# PCE128_rev_C2.net
KiCad netlist of a schematic drawn in EAGLE
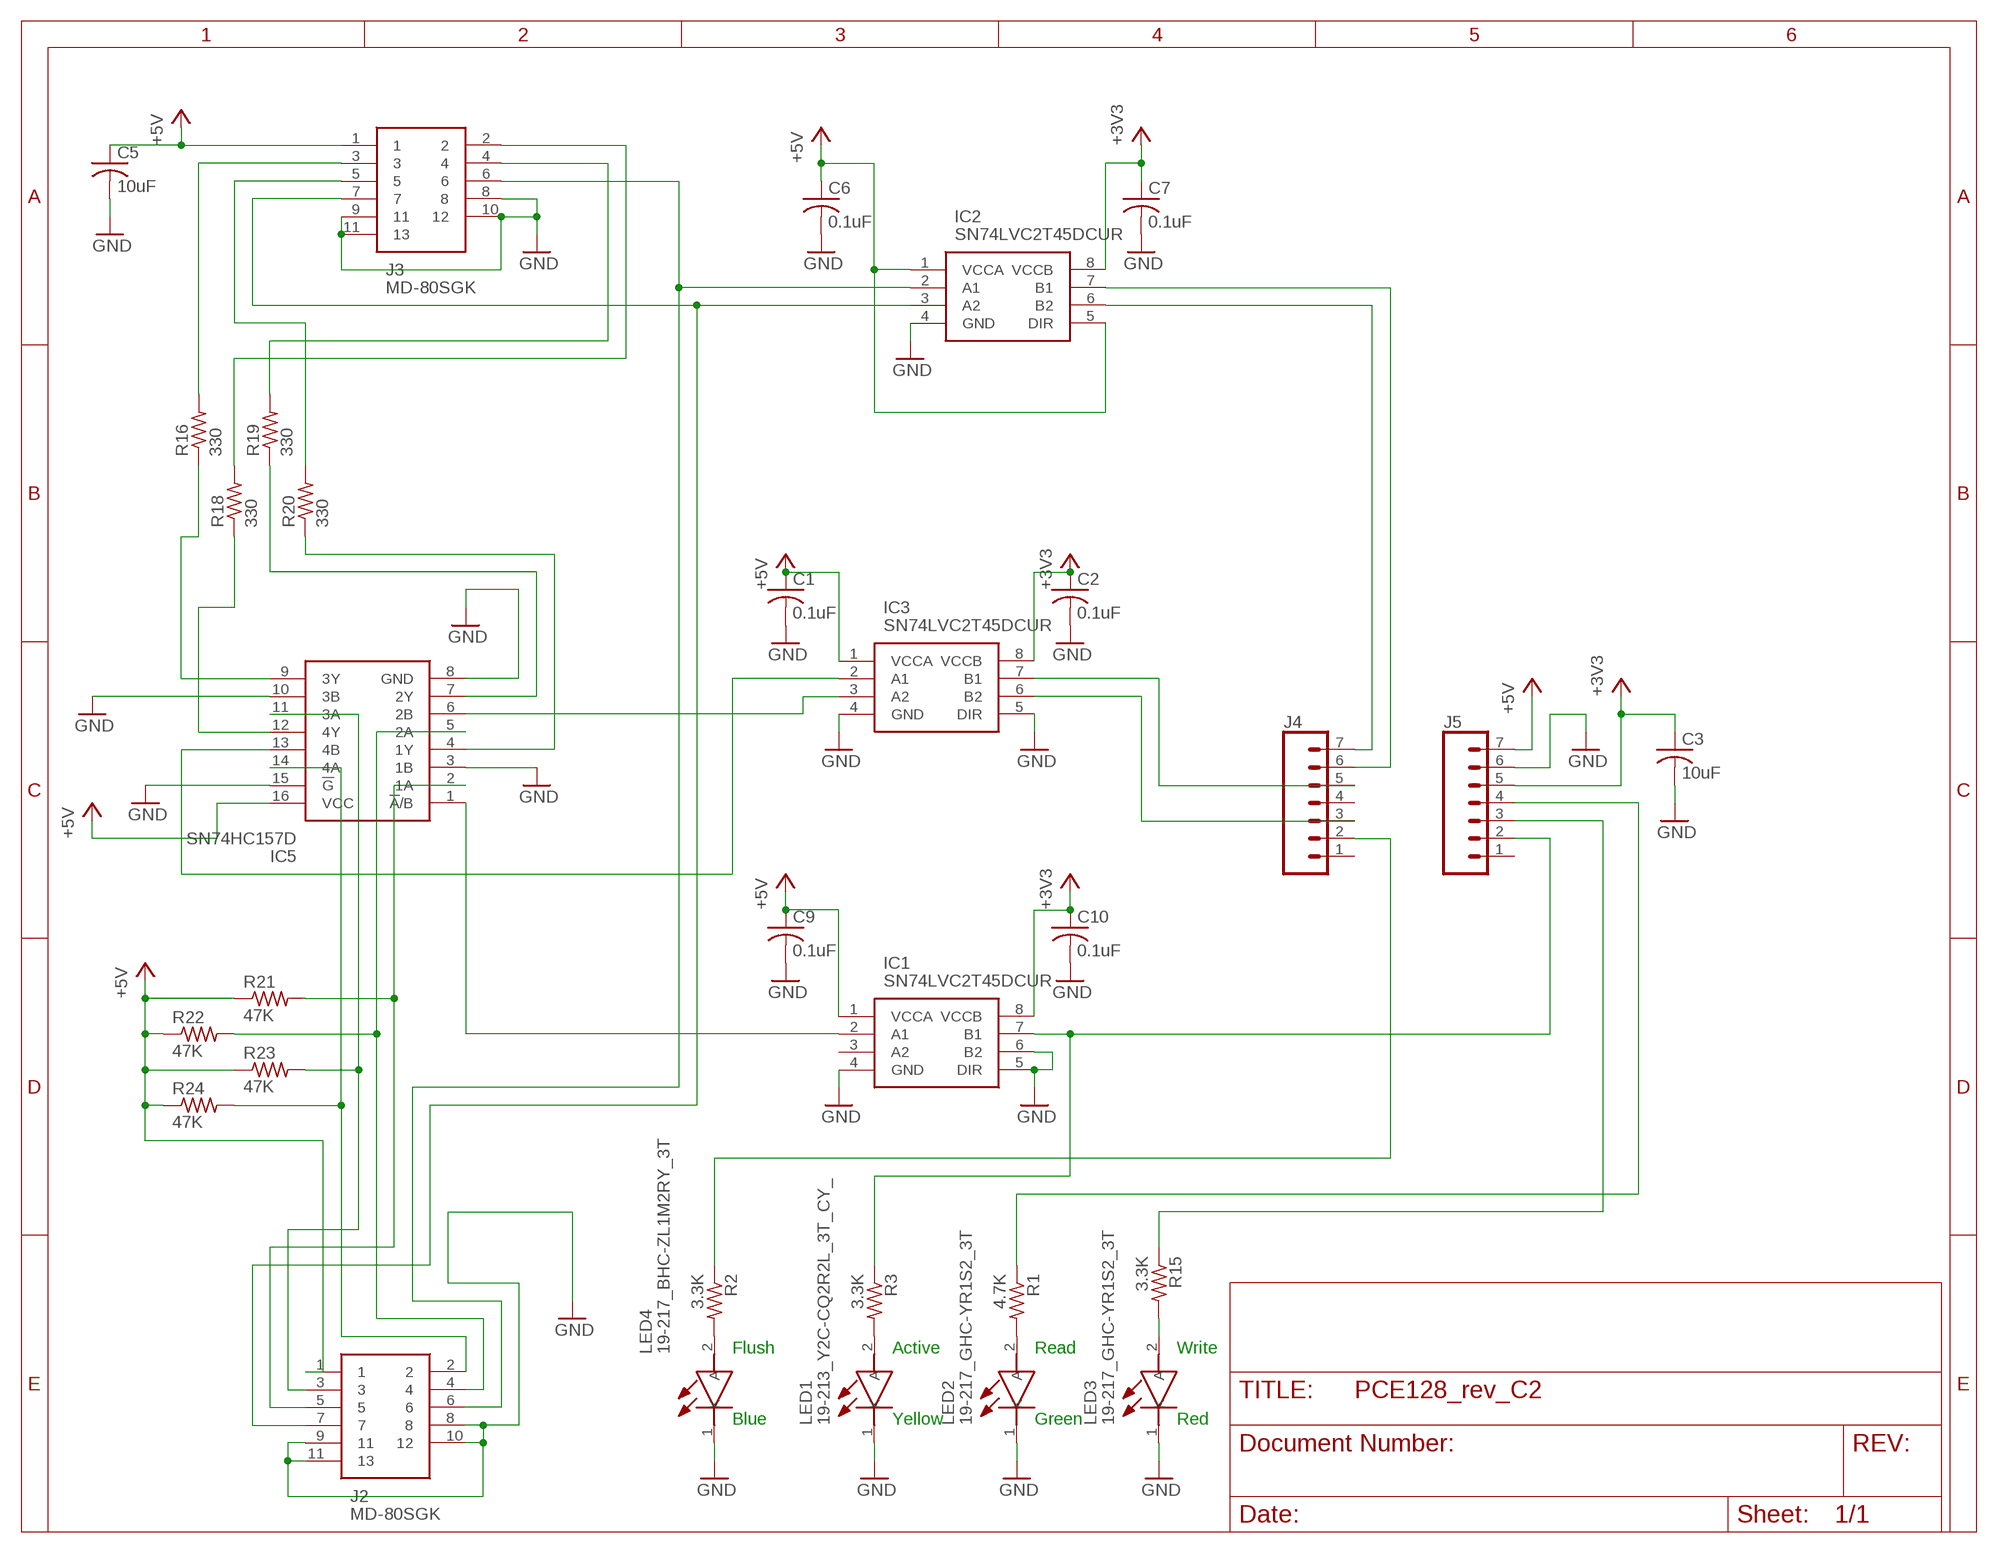
[diagram p0: schematic, sheet 1]

(export (version "E")
  (design (tool "Eeschema 10.0.6"))
  (components
    (comp (ref "C1")
      (value "0.1uF")
      (footprint "eagle-import:C0402")
      (libsource (lib "eagle-import") (part "C-USC0402"))
    )
    (comp (ref "C2")
      (value "0.1uF")
      (footprint "eagle-import:C0402")
      (libsource (lib "eagle-import") (part "C-USC0402"))
    )
    (comp (ref "C3")
      (value "10uF")
      (footprint "eagle-import:C0805")
      (libsource (lib "eagle-import") (part "C-USC0805"))
    )
    (comp (ref "C5")
      (value "10uF")
      (footprint "eagle-import:C0805")
      (libsource (lib "eagle-import") (part "C-USC0805"))
    )
    (comp (ref "C6")
      (value "0.1uF")
      (footprint "eagle-import:C0402")
      (libsource (lib "eagle-import") (part "C-USC0402"))
    )
    (comp (ref "C7")
      (value "0.1uF")
      (footprint "eagle-import:C0402")
      (libsource (lib "eagle-import") (part "C-USC0402"))
    )
    (comp (ref "C9")
      (value "0.1uF")
      (footprint "eagle-import:C0402")
      (libsource (lib "eagle-import") (part "C-USC0402"))
    )
    (comp (ref "C10")
      (value "0.1uF")
      (footprint "eagle-import:C0402")
      (libsource (lib "eagle-import") (part "C-USC0402"))
    )
    (comp (ref "IC1")
      (value "SN74LVC2T45DCUR")
      (footprint "eagle-import:SOP50P310X90-8N")
      (fields (field (name "MOUSER_PART_NUMBER") "595-SN74LVC2T45DCUR"))
      (libsource (lib "eagle-import") (part "SN74LVC2T45DCUR"))
    )
    (comp (ref "IC2")
      (value "SN74LVC2T45DCUR")
      (footprint "eagle-import:SOP50P310X90-8N")
      (fields (field (name "MOUSER_PART_NUMBER") "595-SN74LVC2T45DCUR"))
      (libsource (lib "eagle-import") (part "SN74LVC2T45DCUR"))
    )
    (comp (ref "IC3")
      (value "SN74LVC2T45DCUR")
      (footprint "eagle-import:SOP50P310X90-8N")
      (fields (field (name "MOUSER_PART_NUMBER") "595-SN74LVC2T45DCUR"))
      (libsource (lib "eagle-import") (part "SN74LVC2T45DCUR"))
    )
    (comp (ref "IC5")
      (value "SN74HC157D")
      (footprint "eagle-import:SOIC127P600X175-16N")
      (fields (field (name "MOUSER_PART_NUMBER") "595-SN74HC157D"))
      (libsource (lib "eagle-import") (part "SN74HC157D"))
    )
    (comp (ref "J2")
      (value "MD-80SGK")
      (footprint "eagle-import:MD80SGK")
      (fields (field (name "MOUSER_PART_NUMBER") "490-MD-80SGK"))
      (libsource (lib "eagle-import") (part "MD-80SGK"))
    )
    (comp (ref "J3")
      (value "MD-80SGK")
      (footprint "eagle-import:MD80SGK")
      (fields (field (name "MOUSER_PART_NUMBER") "490-MD-80SGK"))
      (libsource (lib "eagle-import") (part "MD-80SGK"))
    )
    (comp (ref "J4")
      (value "CONN_07NO_SILK")
      (footprint "eagle-import:1X07_NO_SILK")
      (libsource (lib "eagle-import") (part "CONN_07NO_SILK"))
    )
    (comp (ref "J5")
      (value "CONN_07NO_SILK")
      (footprint "eagle-import:1X07_NO_SILK")
      (libsource (lib "eagle-import") (part "CONN_07NO_SILK"))
    )
    (comp (ref "LED1")
      (value "19-213_Y2C-CQ2R2L_3T_CY_")
      (footprint "eagle-import:LEDC1608X50N")
      (fields (field (name "ARROW_PART_NUMBER") "19-213/Y2C-CQ2R2L/3T(CY)"))
      (libsource (lib "eagle-import") (part "19-213_Y2C-CQ2R2L_3T_CY_"))
    )
    (comp (ref "LED2")
      (value "19-217_GHC-YR1S2_3T")
      (footprint "eagle-import:LEDC1608X50N")
      (fields
        (field (name "ARROW_PART_NUMBER") "19-217/GHC-YR1S2/3T")
        (field (name "MOUSER_PART_NUMBER") "638-19217GHCYR1S23T")
      )
      (libsource (lib "eagle-import") (part "19-217_GHC-YR1S2_3T"))
    )
    (comp (ref "LED3")
      (value "19-217_GHC-YR1S2_3T")
      (footprint "eagle-import:LEDC1608X50N")
      (fields
        (field (name "ARROW_PART_NUMBER") "19-217/GHC-YR1S2/3T")
        (field (name "MOUSER_PART_NUMBER") "638-19217GHCYR1S23T")
        (field (name "MANUFACTURER_NAME") "Hubei Kento")
        (field (name "MANUFACTURER_PART_NUMBER") "KT-0603R")
      )
      (libsource (lib "eagle-import") (part "19-217_GHC-YR1S2_3T"))
    )
    (comp (ref "LED4")
      (value "19-217_BHC-ZL1M2RY_3T")
      (footprint "eagle-import:LEDC1608X50N")
      (libsource (lib "eagle-import") (part "19-217_BHC-ZL1M2RY_3T"))
    )
    (comp (ref "R1")
      (value "4.7K")
      (footprint "eagle-import:R0402")
      (libsource (lib "eagle-import") (part "R-US_R0402"))
    )
    (comp (ref "R2")
      (value "3.3K")
      (footprint "eagle-import:R0402")
      (libsource (lib "eagle-import") (part "R-US_R0402"))
    )
    (comp (ref "R3")
      (value "3.3K")
      (footprint "eagle-import:R0402")
      (libsource (lib "eagle-import") (part "R-US_R0402"))
    )
    (comp (ref "R15")
      (value "3.3K")
      (footprint "eagle-import:R0402")
      (libsource (lib "eagle-import") (part "R-US_R0402"))
    )
    (comp (ref "R16")
      (value "330")
      (footprint "eagle-import:R0402")
      (libsource (lib "eagle-import") (part "R-US_R0402"))
    )
    (comp (ref "R18")
      (value "330")
      (footprint "eagle-import:R0402")
      (libsource (lib "eagle-import") (part "R-US_R0402"))
    )
    (comp (ref "R19")
      (value "330")
      (footprint "eagle-import:R0402")
      (libsource (lib "eagle-import") (part "R-US_R0402"))
    )
    (comp (ref "R20")
      (value "330")
      (footprint "eagle-import:R0402")
      (libsource (lib "eagle-import") (part "R-US_R0402"))
    )
    (comp (ref "R21")
      (value "47K")
      (footprint "eagle-import:R0402")
      (libsource (lib "eagle-import") (part "R-US_R0402"))
    )
    (comp (ref "R22")
      (value "47K")
      (footprint "eagle-import:R0402")
      (libsource (lib "eagle-import") (part "R-US_R0402"))
    )
    (comp (ref "R23")
      (value "47K")
      (footprint "eagle-import:R0402")
      (libsource (lib "eagle-import") (part "R-US_R0402"))
    )
    (comp (ref "R24")
      (value "47K")
      (footprint "eagle-import:R0402")
      (libsource (lib "eagle-import") (part "R-US_R0402"))
    )
  )
  (nets
    (net (code "1") (name "+3V3") (class "Default")
      (node (ref "C10") (pin "1") (pinfunction "1_1") (pintype "passive"))
      (node (ref "C2") (pin "1") (pinfunction "1_1") (pintype "passive"))
      (node (ref "C3") (pin "1") (pinfunction "1_1") (pintype "passive"))
      (node (ref "C7") (pin "1") (pinfunction "1_1") (pintype "passive"))
      (node (ref "IC1") (pin "8") (pinfunction "VCCB_8") (pintype "bidirectional"))
      (node (ref "IC2") (pin "8") (pinfunction "VCCB_8") (pintype "bidirectional"))
      (node (ref "IC3") (pin "8") (pinfunction "VCCB_8") (pintype "bidirectional"))
      (node (ref "J5") (pin "5") (pinfunction "5_5") (pintype "passive"))
    )
    (net (code "2") (name "+5V") (class "Default")
      (node (ref "C1") (pin "1") (pinfunction "1_1") (pintype "passive"))
      (node (ref "C5") (pin "1") (pinfunction "1_1") (pintype "passive"))
      (node (ref "C6") (pin "1") (pinfunction "1_1") (pintype "passive"))
      (node (ref "C9") (pin "1") (pinfunction "1_1") (pintype "passive"))
      (node (ref "IC1") (pin "1") (pinfunction "VCCA_1") (pintype "bidirectional"))
      (node (ref "IC2") (pin "1") (pinfunction "VCCA_1") (pintype "bidirectional"))
      (node (ref "IC2") (pin "5") (pinfunction "DIR_5") (pintype "bidirectional"))
      (node (ref "IC3") (pin "1") (pinfunction "VCCA_1") (pintype "bidirectional"))
      (node (ref "IC5") (pin "16") (pinfunction "VCC_16") (pintype "bidirectional"))
      (node (ref "J2") (pin "1") (pinfunction "1_1") (pintype "bidirectional"))
      (node (ref "J3") (pin "1") (pinfunction "1_1") (pintype "bidirectional"))
      (node (ref "J5") (pin "7") (pinfunction "7_7") (pintype "passive"))
      (node (ref "R21") (pin "1") (pinfunction "1_1") (pintype "passive"))
      (node (ref "R22") (pin "1") (pinfunction "1_1") (pintype "passive"))
      (node (ref "R23") (pin "1") (pinfunction "1_1") (pintype "passive"))
      (node (ref "R24") (pin "1") (pinfunction "1_1") (pintype "passive"))
    )
    (net (code "3") (name "GND") (class "Default")
      (node (ref "C1") (pin "2") (pinfunction "2_2") (pintype "passive"))
      (node (ref "C10") (pin "2") (pinfunction "2_2") (pintype "passive"))
      (node (ref "C2") (pin "2") (pinfunction "2_2") (pintype "passive"))
      (node (ref "C3") (pin "2") (pinfunction "2_2") (pintype "passive"))
      (node (ref "C5") (pin "2") (pinfunction "2_2") (pintype "passive"))
      (node (ref "C6") (pin "2") (pinfunction "2_2") (pintype "passive"))
      (node (ref "C7") (pin "2") (pinfunction "2_2") (pintype "passive"))
      (node (ref "C9") (pin "2") (pinfunction "2_2") (pintype "passive"))
      (node (ref "IC1") (pin "4") (pinfunction "GND_4") (pintype "bidirectional"))
      (node (ref "IC1") (pin "5") (pinfunction "DIR_5") (pintype "bidirectional"))
      (node (ref "IC1") (pin "6") (pinfunction "B2_6") (pintype "bidirectional"))
      (node (ref "IC2") (pin "4") (pinfunction "GND_4") (pintype "bidirectional"))
      (node (ref "IC3") (pin "4") (pinfunction "GND_4") (pintype "bidirectional"))
      (node (ref "IC3") (pin "5") (pinfunction "DIR_5") (pintype "bidirectional"))
      (node (ref "IC5") (pin "10") (pinfunction "3B_10") (pintype "bidirectional"))
      (node (ref "IC5") (pin "15") (pinfunction "~{G}_15") (pintype "bidirectional"))
      (node (ref "IC5") (pin "3") (pinfunction "1B_3") (pintype "bidirectional"))
      (node (ref "IC5") (pin "8") (pinfunction "GND_8") (pintype "bidirectional"))
      (node (ref "J2") (pin "10") (pinfunction "12_10") (pintype "bidirectional"))
      (node (ref "J2") (pin "11") (pinfunction "13_11") (pintype "bidirectional"))
      (node (ref "J2") (pin "8") (pinfunction "8_8") (pintype "bidirectional"))
      (node (ref "J2") (pin "9") (pinfunction "11_9") (pintype "bidirectional"))
      (node (ref "J3") (pin "10") (pinfunction "12_10") (pintype "bidirectional"))
      (node (ref "J3") (pin "11") (pinfunction "13_11") (pintype "bidirectional"))
      (node (ref "J3") (pin "8") (pinfunction "8_8") (pintype "bidirectional"))
      (node (ref "J3") (pin "9") (pinfunction "11_9") (pintype "bidirectional"))
      (node (ref "J5") (pin "6") (pinfunction "6_6") (pintype "passive"))
      (node (ref "LED1") (pin "1") (pinfunction "K_1") (pintype "bidirectional"))
      (node (ref "LED2") (pin "1") (pinfunction "K_1") (pintype "bidirectional"))
      (node (ref "LED3") (pin "1") (pinfunction "K_1") (pintype "bidirectional"))
      (node (ref "LED4") (pin "1") (pinfunction "K_1") (pintype "bidirectional"))
    )
    (net (code "4") (name "Net-(IC1-A1)") (class "Default")
      (node (ref "IC1") (pin "2") (pinfunction "A1_2") (pintype "bidirectional"))
      (node (ref "IC5") (pin "1") (pinfunction "~{A}/B_1") (pintype "bidirectional"))
    )
    (net (code "5") (name "Net-(IC1-B1)") (class "Default")
      (node (ref "IC1") (pin "7") (pinfunction "B1_7") (pintype "bidirectional"))
      (node (ref "J5") (pin "2") (pinfunction "2_2") (pintype "passive"))
      (node (ref "R3") (pin "1") (pinfunction "1_1") (pintype "passive"))
    )
    (net (code "6") (name "Net-(IC2-A1)") (class "Default")
      (node (ref "IC2") (pin "2") (pinfunction "A1_2") (pintype "bidirectional"))
      (node (ref "J2") (pin "6") (pinfunction "6_6") (pintype "bidirectional"))
      (node (ref "J3") (pin "6") (pinfunction "6_6") (pintype "bidirectional"))
    )
    (net (code "7") (name "Net-(IC2-A2)") (class "Default")
      (node (ref "IC2") (pin "3") (pinfunction "A2_3") (pintype "bidirectional"))
      (node (ref "J2") (pin "7") (pinfunction "7_7") (pintype "bidirectional"))
      (node (ref "J3") (pin "7") (pinfunction "7_7") (pintype "bidirectional"))
    )
    (net (code "8") (name "Net-(IC2-B1)") (class "Default")
      (node (ref "IC2") (pin "7") (pinfunction "B1_7") (pintype "bidirectional"))
      (node (ref "J4") (pin "6") (pinfunction "6_6") (pintype "passive"))
    )
    (net (code "9") (name "Net-(IC2-B2)") (class "Default")
      (node (ref "IC2") (pin "6") (pinfunction "B2_6") (pintype "bidirectional"))
      (node (ref "J4") (pin "7") (pinfunction "7_7") (pintype "passive"))
    )
    (net (code "10") (name "Net-(IC3-A1)") (class "Default")
      (node (ref "IC3") (pin "2") (pinfunction "A1_2") (pintype "bidirectional"))
      (node (ref "IC5") (pin "13") (pinfunction "4B_13") (pintype "bidirectional"))
    )
    (net (code "11") (name "Net-(IC3-A2)") (class "Default")
      (node (ref "IC3") (pin "3") (pinfunction "A2_3") (pintype "bidirectional"))
      (node (ref "IC5") (pin "6") (pinfunction "2B_6") (pintype "bidirectional"))
    )
    (net (code "12") (name "Net-(IC3-B1)") (class "Default")
      (node (ref "IC3") (pin "7") (pinfunction "B1_7") (pintype "bidirectional"))
      (node (ref "J4") (pin "5") (pinfunction "5_5") (pintype "passive"))
    )
    (net (code "13") (name "Net-(IC3-B2)") (class "Default")
      (node (ref "IC3") (pin "6") (pinfunction "B2_6") (pintype "bidirectional"))
      (node (ref "J4") (pin "3") (pinfunction "3_3") (pintype "passive"))
    )
    (net (code "14") (name "Net-(IC5-1A)") (class "Default")
      (node (ref "IC5") (pin "2") (pinfunction "1A_2") (pintype "bidirectional"))
      (node (ref "J2") (pin "5") (pinfunction "5_5") (pintype "bidirectional"))
      (node (ref "R21") (pin "2") (pinfunction "2_2") (pintype "passive"))
    )
    (net (code "15") (name "Net-(IC5-1Y)") (class "Default")
      (node (ref "IC5") (pin "4") (pinfunction "1Y_4") (pintype "bidirectional"))
      (node (ref "R20") (pin "1") (pinfunction "1_1") (pintype "passive"))
    )
    (net (code "16") (name "Net-(IC5-2A)") (class "Default")
      (node (ref "IC5") (pin "5") (pinfunction "2A_5") (pintype "bidirectional"))
      (node (ref "J2") (pin "4") (pinfunction "4_4") (pintype "bidirectional"))
      (node (ref "R22") (pin "2") (pinfunction "2_2") (pintype "passive"))
    )
    (net (code "17") (name "Net-(IC5-2Y)") (class "Default")
      (node (ref "IC5") (pin "7") (pinfunction "2Y_7") (pintype "bidirectional"))
      (node (ref "R19") (pin "1") (pinfunction "1_1") (pintype "passive"))
    )
    (net (code "18") (name "Net-(IC5-3A)") (class "Default")
      (node (ref "IC5") (pin "11") (pinfunction "3A_11") (pintype "bidirectional"))
      (node (ref "J2") (pin "3") (pinfunction "3_3") (pintype "bidirectional"))
      (node (ref "R23") (pin "2") (pinfunction "2_2") (pintype "passive"))
    )
    (net (code "19") (name "Net-(IC5-3Y)") (class "Default")
      (node (ref "IC5") (pin "9") (pinfunction "3Y_9") (pintype "bidirectional"))
      (node (ref "R16") (pin "1") (pinfunction "1_1") (pintype "passive"))
    )
    (net (code "20") (name "Net-(IC5-4A)") (class "Default")
      (node (ref "IC5") (pin "14") (pinfunction "4A_14") (pintype "bidirectional"))
      (node (ref "J2") (pin "2") (pinfunction "2_2") (pintype "bidirectional"))
      (node (ref "R24") (pin "2") (pinfunction "2_2") (pintype "passive"))
    )
    (net (code "21") (name "Net-(IC5-4Y)") (class "Default")
      (node (ref "IC5") (pin "12") (pinfunction "4Y_12") (pintype "bidirectional"))
      (node (ref "R18") (pin "1") (pinfunction "1_1") (pintype "passive"))
    )
    (net (code "22") (name "Net-(J3-Pad2)") (class "Default")
      (node (ref "J3") (pin "2") (pinfunction "2_2") (pintype "bidirectional"))
      (node (ref "R18") (pin "2") (pinfunction "2_2") (pintype "passive"))
    )
    (net (code "23") (name "Net-(J3-Pad3)") (class "Default")
      (node (ref "J3") (pin "3") (pinfunction "3_3") (pintype "bidirectional"))
      (node (ref "R16") (pin "2") (pinfunction "2_2") (pintype "passive"))
    )
    (net (code "24") (name "Net-(J3-Pad4)") (class "Default")
      (node (ref "J3") (pin "4") (pinfunction "4_4") (pintype "bidirectional"))
      (node (ref "R19") (pin "2") (pinfunction "2_2") (pintype "passive"))
    )
    (net (code "25") (name "Net-(J3-Pad5)") (class "Default")
      (node (ref "J3") (pin "5") (pinfunction "5_5") (pintype "bidirectional"))
      (node (ref "R20") (pin "2") (pinfunction "2_2") (pintype "passive"))
    )
    (net (code "26") (name "Net-(J4-Pad2)") (class "Default")
      (node (ref "J4") (pin "2") (pinfunction "2_2") (pintype "passive"))
      (node (ref "R2") (pin "1") (pinfunction "1_1") (pintype "passive"))
    )
    (net (code "27") (name "Net-(J5-Pad3)") (class "Default")
      (node (ref "J5") (pin "3") (pinfunction "3_3") (pintype "passive"))
      (node (ref "R15") (pin "1") (pinfunction "1_1") (pintype "passive"))
    )
    (net (code "28") (name "Net-(J5-Pad4)") (class "Default")
      (node (ref "J5") (pin "4") (pinfunction "4_4") (pintype "passive"))
      (node (ref "R1") (pin "1") (pinfunction "1_1") (pintype "passive"))
    )
    (net (code "29") (name "Net-(LED1-A)") (class "Default")
      (node (ref "LED1") (pin "2") (pinfunction "A_2") (pintype "bidirectional"))
      (node (ref "R3") (pin "2") (pinfunction "2_2") (pintype "passive"))
    )
    (net (code "30") (name "Net-(LED2-A)") (class "Default")
      (node (ref "LED2") (pin "2") (pinfunction "A_2") (pintype "bidirectional"))
      (node (ref "R1") (pin "2") (pinfunction "2_2") (pintype "passive"))
    )
    (net (code "31") (name "Net-(LED3-A)") (class "Default")
      (node (ref "LED3") (pin "2") (pinfunction "A_2") (pintype "bidirectional"))
      (node (ref "R15") (pin "2") (pinfunction "2_2") (pintype "passive"))
    )
    (net (code "32") (name "Net-(LED4-A)") (class "Default")
      (node (ref "LED4") (pin "2") (pinfunction "A_2") (pintype "bidirectional"))
      (node (ref "R2") (pin "2") (pinfunction "2_2") (pintype "passive"))
    )
    (net (code "33") (name "unconnected-(IC1-A2-Pad3)") (class "Default")
      (node (ref "IC1") (pin "3") (pinfunction "A2_3") (pintype "bidirectional"))
    )
    (net (code "34") (name "unconnected-(J4-Pad1)") (class "Default")
      (node (ref "J4") (pin "1") (pinfunction "1_1") (pintype "passive"))
    )
    (net (code "35") (name "unconnected-(J4-Pad4)") (class "Default")
      (node (ref "J4") (pin "4") (pinfunction "4_4") (pintype "passive"))
    )
    (net (code "36") (name "unconnected-(J5-Pad1)") (class "Default")
      (node (ref "J5") (pin "1") (pinfunction "1_1") (pintype "passive"))
    )
  )
)
